# untitled.net
KiCad netlist of a schematic drawn in EAGLE
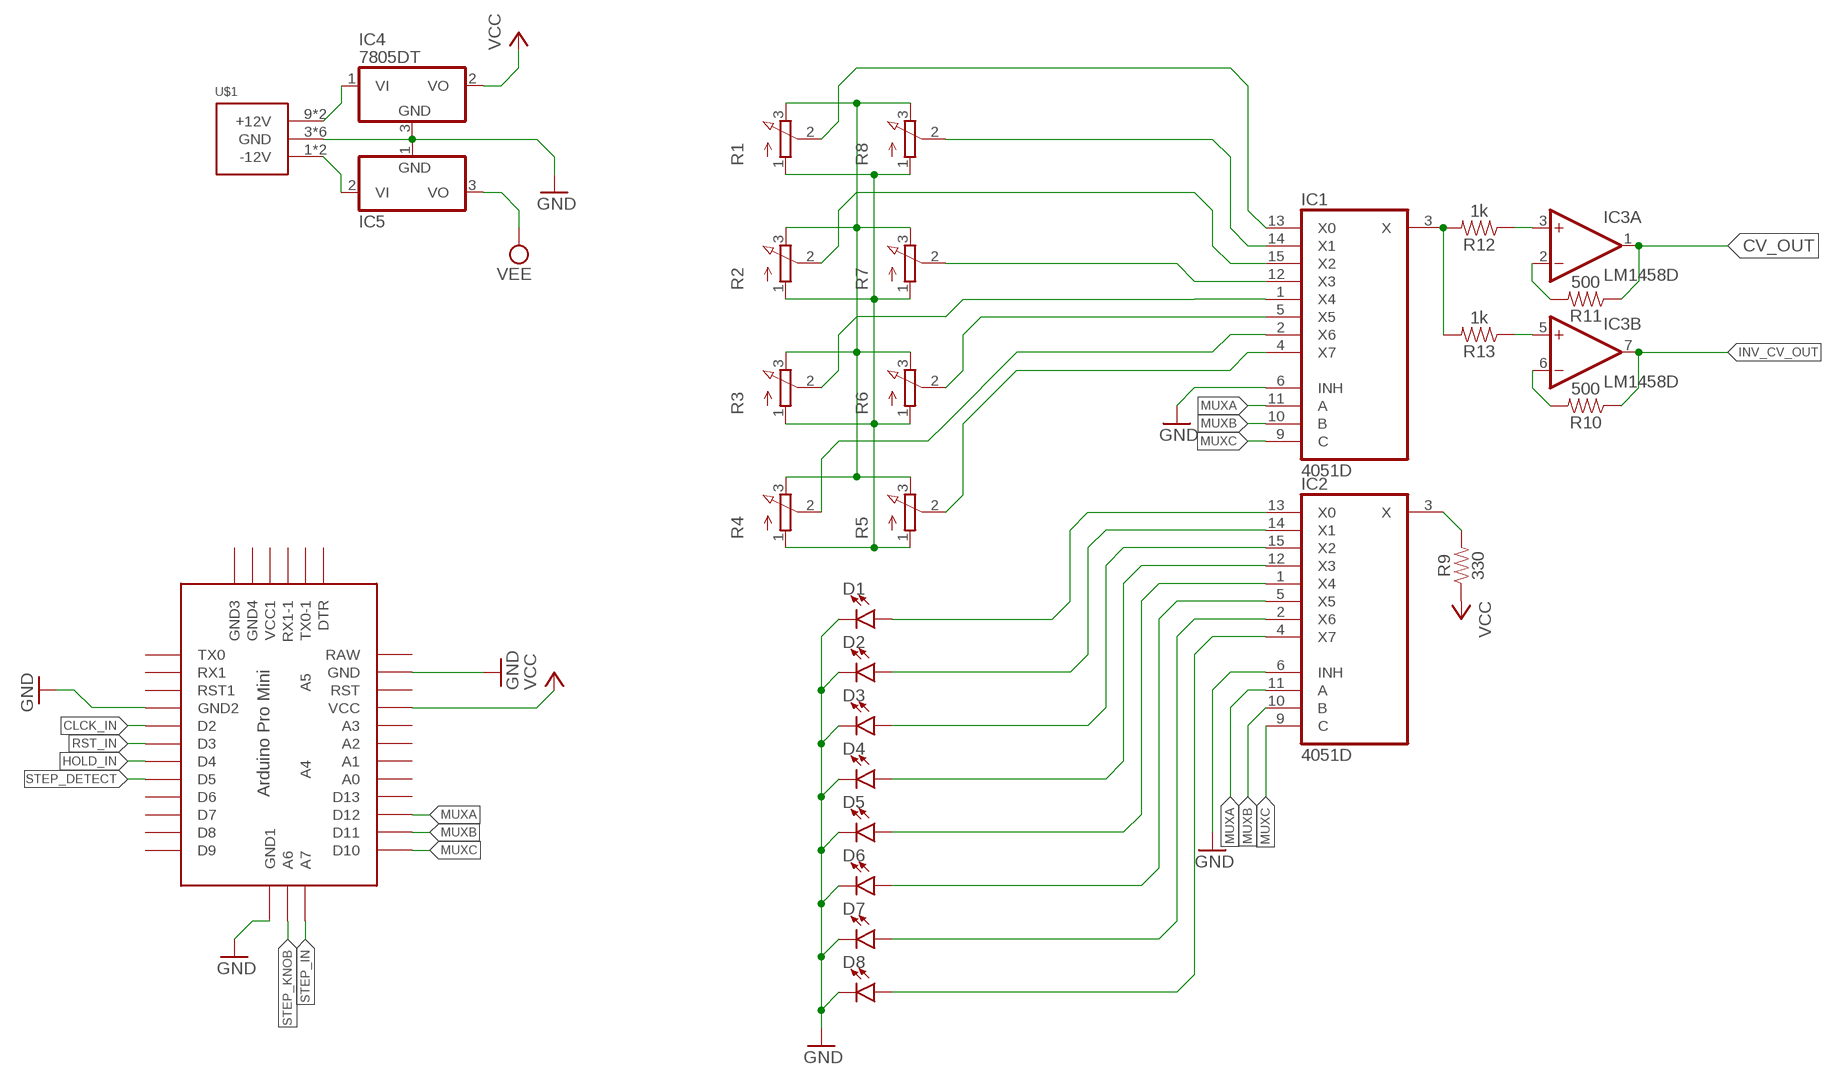
[diagram p0: schematic, sheet 1]

(export (version "E")
  (design (tool "Eeschema 10.0.6"))
  (components
    (comp (ref "D1")
      (value "LED5MM")
      (footprint "eagle-import:LED_5MM")
      (libsource (lib "eagle-import") (part "LED5MM"))
    )
    (comp (ref "D2")
      (value "LED5MM")
      (footprint "eagle-import:LED_5MM")
      (libsource (lib "eagle-import") (part "LED5MM"))
    )
    (comp (ref "D3")
      (value "LED5MM")
      (footprint "eagle-import:LED_5MM")
      (libsource (lib "eagle-import") (part "LED5MM"))
    )
    (comp (ref "D4")
      (value "LED5MM")
      (footprint "eagle-import:LED_5MM")
      (libsource (lib "eagle-import") (part "LED5MM"))
    )
    (comp (ref "D5")
      (value "LED5MM")
      (footprint "eagle-import:LED_5MM")
      (libsource (lib "eagle-import") (part "LED5MM"))
    )
    (comp (ref "D6")
      (value "LED5MM")
      (footprint "eagle-import:LED_5MM")
      (libsource (lib "eagle-import") (part "LED5MM"))
    )
    (comp (ref "D7")
      (value "LED5MM")
      (footprint "eagle-import:LED_5MM")
      (libsource (lib "eagle-import") (part "LED5MM"))
    )
    (comp (ref "D8")
      (value "LED5MM")
      (footprint "eagle-import:LED_5MM")
      (libsource (lib "eagle-import") (part "LED5MM"))
    )
    (comp (ref "IC1")
      (value "4051D")
      (footprint "eagle-import:SO16")
      (libsource (lib "eagle-import") (part "4051D"))
    )
    (comp (ref "IC2")
      (value "4051D")
      (footprint "eagle-import:SO16")
      (libsource (lib "eagle-import") (part "4051D"))
    )
    (comp (ref "IC3")
      (value "LM1458D")
      (footprint "eagle-import:SO08")
      (libsource (lib "eagle-import") (part "1458DLM"))
    )
    (comp (ref "IC4")
      (value "7805DT")
      (footprint "eagle-import:TO252")
      (libsource (lib "eagle-import") (part "78DT05"))
    )
    (comp (ref "IC5")
      (value "7905T")
      (footprint "eagle-import:TO220H")
      (libsource (lib "eagle-import") (part "79T05"))
    )
    (comp (ref "R1")
      (value "3RP/1610N")
      (footprint "eagle-import:3RP_1610N")
      (libsource (lib "eagle-import") (part "3RP/1610N"))
    )
    (comp (ref "R2")
      (value "3RP/1610N")
      (footprint "eagle-import:3RP_1610N")
      (libsource (lib "eagle-import") (part "3RP/1610N"))
    )
    (comp (ref "R3")
      (value "3RP/1610N")
      (footprint "eagle-import:3RP_1610N")
      (libsource (lib "eagle-import") (part "3RP/1610N"))
    )
    (comp (ref "R4")
      (value "3RP/1610N")
      (footprint "eagle-import:3RP_1610N")
      (libsource (lib "eagle-import") (part "3RP/1610N"))
    )
    (comp (ref "R5")
      (value "3RP/1610N")
      (footprint "eagle-import:3RP_1610N")
      (libsource (lib "eagle-import") (part "3RP/1610N"))
    )
    (comp (ref "R6")
      (value "3RP/1610N")
      (footprint "eagle-import:3RP_1610N")
      (libsource (lib "eagle-import") (part "3RP/1610N"))
    )
    (comp (ref "R7")
      (value "3RP/1610N")
      (footprint "eagle-import:3RP_1610N")
      (libsource (lib "eagle-import") (part "3RP/1610N"))
    )
    (comp (ref "R8")
      (value "3RP/1610N")
      (footprint "eagle-import:3RP_1610N")
      (libsource (lib "eagle-import") (part "3RP/1610N"))
    )
    (comp (ref "R9")
      (value "330")
      (footprint "eagle-import:AXIAL-0.3")
      (libsource (lib "eagle-import") (part "330OHM-HORIZ-1/10W-5%"))
    )
    (comp (ref "R10")
      (value "500")
      (footprint "eagle-import:AXIAL-0.3")
      (libsource (lib "eagle-import") (part "330OHM-HORIZ-1/10W-5%"))
    )
    (comp (ref "R11")
      (value "500")
      (footprint "eagle-import:AXIAL-0.3")
      (libsource (lib "eagle-import") (part "330OHM-HORIZ-1/10W-5%"))
    )
    (comp (ref "R12")
      (value "1k")
      (footprint "eagle-import:AXIAL-0.3")
      (libsource (lib "eagle-import") (part "330OHM-HORIZ-1/10W-5%"))
    )
    (comp (ref "R13")
      (value "1k")
      (footprint "eagle-import:AXIAL-0.3")
      (libsource (lib "eagle-import") (part "330OHM-HORIZ-1/10W-5%"))
    )
    (comp (ref "U$1")
      (value "POWER_SIMPLE10")
      (footprint "eagle-import:POWER_10")
      (libsource (lib "eagle-import") (part "POWER_SIMPLE10"))
    )
    (comp (ref "U$2")
      (value "ABK-PRO-MINI")
      (footprint "eagle-import:ABK-PRO-MINI")
      (libsource (lib "eagle-import") (part "ABK-PRO-MINI"))
    )
  )
  (nets
    (net (code "1") (name "CLCK_IN") (class "Default")
      (node (ref "U$2") (pin "D2") (pinfunction "D2_D2") (pintype "bidirectional"))
    )
    (net (code "2") (name "CV_OUT") (class "Default")
      (node (ref "IC3") (pin "1") (pinfunction "OUT_1") (pintype "output"))
      (node (ref "R11") (pin "P$1") (pinfunction "1_P$1") (pintype "passive"))
    )
    (net (code "3") (name "GND") (class "Default")
      (node (ref "D1") (pin "K") (pinfunction "C_K") (pintype "passive"))
      (node (ref "D2") (pin "K") (pinfunction "C_K") (pintype "passive"))
      (node (ref "D3") (pin "K") (pinfunction "C_K") (pintype "passive"))
      (node (ref "D4") (pin "K") (pinfunction "C_K") (pintype "passive"))
      (node (ref "D5") (pin "K") (pinfunction "C_K") (pintype "passive"))
      (node (ref "D6") (pin "K") (pinfunction "C_K") (pintype "passive"))
      (node (ref "D7") (pin "K") (pinfunction "C_K") (pintype "passive"))
      (node (ref "D8") (pin "K") (pinfunction "C_K") (pintype "passive"))
      (node (ref "IC1") (pin "6") (pinfunction "INH_6") (pintype "input"))
      (node (ref "IC2") (pin "6") (pinfunction "INH_6") (pintype "input"))
      (node (ref "IC4") (pin "3") (pinfunction "GND_3") (pintype "passive"))
      (node (ref "IC5") (pin "1") (pinfunction "GND_1") (pintype "passive"))
      (node (ref "U$1") (pin "3") (pinfunction "GND_3") (pintype "bidirectional"))
      (node (ref "U$1") (pin "4") (pinfunction "GND_4") (pintype "bidirectional"))
      (node (ref "U$1") (pin "5") (pinfunction "GND_5") (pintype "bidirectional"))
      (node (ref "U$1") (pin "6") (pinfunction "GND_6") (pintype "bidirectional"))
      (node (ref "U$1") (pin "7") (pinfunction "GND_7") (pintype "bidirectional"))
      (node (ref "U$1") (pin "8") (pinfunction "GND_8") (pintype "bidirectional"))
      (node (ref "U$2") (pin "GND") (pinfunction "GND_GND") (pintype "bidirectional"))
      (node (ref "U$2") (pin "GND1") (pinfunction "GND2_GND1") (pintype "bidirectional"))
      (node (ref "U$2") (pin "GND4") (pinfunction "GND1_GND4") (pintype "bidirectional"))
    )
    (net (code "4") (name "HOLD_IN") (class "Default")
      (node (ref "U$2") (pin "D4") (pinfunction "D4_D4") (pintype "bidirectional"))
    )
    (net (code "5") (name "INV_CV_OUT") (class "Default")
      (node (ref "IC3") (pin "7") (pinfunction "OUT_7") (pintype "output"))
      (node (ref "R10") (pin "P$1") (pinfunction "1_P$1") (pintype "passive"))
    )
    (net (code "6") (name "MUXA") (class "Default")
      (node (ref "IC1") (pin "11") (pinfunction "A_11") (pintype "input"))
      (node (ref "IC2") (pin "11") (pinfunction "A_11") (pintype "input"))
      (node (ref "U$2") (pin "D12") (pinfunction "D12_D12") (pintype "bidirectional"))
    )
    (net (code "7") (name "MUXB") (class "Default")
      (node (ref "IC1") (pin "10") (pinfunction "B_10") (pintype "input"))
      (node (ref "IC2") (pin "10") (pinfunction "B_10") (pintype "input"))
      (node (ref "U$2") (pin "D11") (pinfunction "D11_D11") (pintype "bidirectional"))
    )
    (net (code "8") (name "MUXC") (class "Default")
      (node (ref "IC1") (pin "9") (pinfunction "C_9") (pintype "input"))
      (node (ref "IC2") (pin "9") (pinfunction "C_9") (pintype "input"))
      (node (ref "U$2") (pin "D10") (pinfunction "D10_D10") (pintype "bidirectional"))
    )
    (net (code "9") (name "Net-(IC1A-X)") (class "Default")
      (node (ref "IC1") (pin "3") (pinfunction "X_3") (pintype "bidirectional"))
      (node (ref "R12") (pin "P$2") (pinfunction "2_P$2") (pintype "passive"))
      (node (ref "R13") (pin "P$2") (pinfunction "2_P$2") (pintype "passive"))
    )
    (net (code "10") (name "Net-(IC1A-X0)") (class "Default")
      (node (ref "IC1") (pin "13") (pinfunction "X0_13") (pintype "bidirectional"))
      (node (ref "R1") (pin "2") (pinfunction "S_2") (pintype "passive"))
    )
    (net (code "11") (name "Net-(IC1A-X1)") (class "Default")
      (node (ref "IC1") (pin "14") (pinfunction "X1_14") (pintype "bidirectional"))
      (node (ref "R8") (pin "2") (pinfunction "S_2") (pintype "passive"))
    )
    (net (code "12") (name "Net-(IC1A-X2)") (class "Default")
      (node (ref "IC1") (pin "15") (pinfunction "X2_15") (pintype "bidirectional"))
      (node (ref "R2") (pin "2") (pinfunction "S_2") (pintype "passive"))
    )
    (net (code "13") (name "Net-(IC1A-X3)") (class "Default")
      (node (ref "IC1") (pin "12") (pinfunction "X3_12") (pintype "bidirectional"))
      (node (ref "R7") (pin "2") (pinfunction "S_2") (pintype "passive"))
    )
    (net (code "14") (name "Net-(IC1A-X4)") (class "Default")
      (node (ref "IC1") (pin "1") (pinfunction "X4_1") (pintype "bidirectional"))
      (node (ref "R3") (pin "2") (pinfunction "S_2") (pintype "passive"))
    )
    (net (code "15") (name "Net-(IC1A-X5)") (class "Default")
      (node (ref "IC1") (pin "5") (pinfunction "X5_5") (pintype "bidirectional"))
      (node (ref "R6") (pin "2") (pinfunction "S_2") (pintype "passive"))
    )
    (net (code "16") (name "Net-(IC1A-X6)") (class "Default")
      (node (ref "IC1") (pin "2") (pinfunction "X6_2") (pintype "bidirectional"))
      (node (ref "R4") (pin "2") (pinfunction "S_2") (pintype "passive"))
    )
    (net (code "17") (name "Net-(IC1A-X7)") (class "Default")
      (node (ref "IC1") (pin "4") (pinfunction "X7_4") (pintype "bidirectional"))
      (node (ref "R5") (pin "2") (pinfunction "S_2") (pintype "passive"))
    )
    (net (code "18") (name "Net-(IC2A-X)") (class "Default")
      (node (ref "IC2") (pin "3") (pinfunction "X_3") (pintype "bidirectional"))
      (node (ref "R9") (pin "P$2") (pinfunction "2_P$2") (pintype "passive"))
    )
    (net (code "19") (name "Net-(IC2A-X0)") (class "Default")
      (node (ref "D1") (pin "A") (pinfunction "A_A") (pintype "passive"))
      (node (ref "IC2") (pin "13") (pinfunction "X0_13") (pintype "bidirectional"))
    )
    (net (code "20") (name "Net-(IC2A-X1)") (class "Default")
      (node (ref "D2") (pin "A") (pinfunction "A_A") (pintype "passive"))
      (node (ref "IC2") (pin "14") (pinfunction "X1_14") (pintype "bidirectional"))
    )
    (net (code "21") (name "Net-(IC2A-X2)") (class "Default")
      (node (ref "D3") (pin "A") (pinfunction "A_A") (pintype "passive"))
      (node (ref "IC2") (pin "15") (pinfunction "X2_15") (pintype "bidirectional"))
    )
    (net (code "22") (name "Net-(IC2A-X3)") (class "Default")
      (node (ref "D4") (pin "A") (pinfunction "A_A") (pintype "passive"))
      (node (ref "IC2") (pin "12") (pinfunction "X3_12") (pintype "bidirectional"))
    )
    (net (code "23") (name "Net-(IC2A-X4)") (class "Default")
      (node (ref "D5") (pin "A") (pinfunction "A_A") (pintype "passive"))
      (node (ref "IC2") (pin "1") (pinfunction "X4_1") (pintype "bidirectional"))
    )
    (net (code "24") (name "Net-(IC2A-X5)") (class "Default")
      (node (ref "D6") (pin "A") (pinfunction "A_A") (pintype "passive"))
      (node (ref "IC2") (pin "5") (pinfunction "X5_5") (pintype "bidirectional"))
    )
    (net (code "25") (name "Net-(IC2A-X6)") (class "Default")
      (node (ref "D7") (pin "A") (pinfunction "A_A") (pintype "passive"))
      (node (ref "IC2") (pin "2") (pinfunction "X6_2") (pintype "bidirectional"))
    )
    (net (code "26") (name "Net-(IC2A-X7)") (class "Default")
      (node (ref "D8") (pin "A") (pinfunction "A_A") (pintype "passive"))
      (node (ref "IC2") (pin "4") (pinfunction "X7_4") (pintype "bidirectional"))
    )
    (net (code "27") (name "Net-(IC3A-+IN)") (class "Default")
      (node (ref "IC3") (pin "3") (pinfunction "+IN_3") (pintype "input"))
      (node (ref "R12") (pin "P$1") (pinfunction "1_P$1") (pintype "passive"))
    )
    (net (code "28") (name "Net-(IC3A--IN)") (class "Default")
      (node (ref "IC3") (pin "2") (pinfunction "-IN_2") (pintype "input"))
      (node (ref "R11") (pin "P$2") (pinfunction "2_P$2") (pintype "passive"))
    )
    (net (code "29") (name "Net-(IC3B-+IN)") (class "Default")
      (node (ref "IC3") (pin "5") (pinfunction "+IN_5") (pintype "input"))
      (node (ref "R13") (pin "P$1") (pinfunction "1_P$1") (pintype "passive"))
    )
    (net (code "30") (name "Net-(IC3B--IN)") (class "Default")
      (node (ref "IC3") (pin "6") (pinfunction "-IN_6") (pintype "input"))
      (node (ref "R10") (pin "P$2") (pinfunction "2_P$2") (pintype "passive"))
    )
    (net (code "31") (name "Net-(IC4-VI)") (class "Default")
      (node (ref "IC4") (pin "1") (pinfunction "VI_1") (pintype "input"))
      (node (ref "U$1") (pin "10") (pinfunction "+12V_10") (pintype "bidirectional"))
      (node (ref "U$1") (pin "9") (pinfunction "+12V_9") (pintype "bidirectional"))
    )
    (net (code "32") (name "Net-(IC5-VI)") (class "Default")
      (node (ref "IC5") (pin "2") (pinfunction "VI_2") (pintype "input"))
      (node (ref "U$1") (pin "1") (pinfunction "-12V_1") (pintype "bidirectional"))
      (node (ref "U$1") (pin "2") (pinfunction "-12V_2") (pintype "bidirectional"))
    )
    (net (code "33") (name "Net-(R1-A)") (class "Default")
      (node (ref "R1") (pin "1") (pinfunction "A_1") (pintype "passive"))
      (node (ref "R2") (pin "1") (pinfunction "A_1") (pintype "passive"))
      (node (ref "R3") (pin "1") (pinfunction "A_1") (pintype "passive"))
      (node (ref "R4") (pin "1") (pinfunction "A_1") (pintype "passive"))
      (node (ref "R5") (pin "1") (pinfunction "A_1") (pintype "passive"))
      (node (ref "R6") (pin "1") (pinfunction "A_1") (pintype "passive"))
      (node (ref "R7") (pin "1") (pinfunction "A_1") (pintype "passive"))
      (node (ref "R8") (pin "1") (pinfunction "A_1") (pintype "passive"))
    )
    (net (code "34") (name "Net-(R1-E)") (class "Default")
      (node (ref "R1") (pin "3") (pinfunction "E_3") (pintype "passive"))
      (node (ref "R2") (pin "3") (pinfunction "E_3") (pintype "passive"))
      (node (ref "R3") (pin "3") (pinfunction "E_3") (pintype "passive"))
      (node (ref "R4") (pin "3") (pinfunction "E_3") (pintype "passive"))
      (node (ref "R5") (pin "3") (pinfunction "E_3") (pintype "passive"))
      (node (ref "R6") (pin "3") (pinfunction "E_3") (pintype "passive"))
      (node (ref "R7") (pin "3") (pinfunction "E_3") (pintype "passive"))
      (node (ref "R8") (pin "3") (pinfunction "E_3") (pintype "passive"))
    )
    (net (code "35") (name "RST_IN") (class "Default")
      (node (ref "U$2") (pin "D3") (pinfunction "D3_D3") (pintype "bidirectional"))
    )
    (net (code "36") (name "STEP_DETECT") (class "Default")
      (node (ref "U$2") (pin "D5") (pinfunction "D5_D5") (pintype "bidirectional"))
    )
    (net (code "37") (name "STEP_IN") (class "Default")
      (node (ref "U$2") (pin "A7") (pinfunction "A7_A7") (pintype "bidirectional"))
    )
    (net (code "38") (name "STEP_KNOB") (class "Default")
      (node (ref "U$2") (pin "A6") (pinfunction "A6_A6") (pintype "bidirectional"))
    )
    (net (code "39") (name "VCC") (class "Default")
      (node (ref "IC4") (pin "2") (pinfunction "VO_2") (pintype "passive"))
      (node (ref "R9") (pin "P$1") (pinfunction "1_P$1") (pintype "passive"))
      (node (ref "U$2") (pin "VCC") (pinfunction "VCC_VCC") (pintype "bidirectional"))
    )
    (net (code "40") (name "VEE") (class "Default")
      (node (ref "IC5") (pin "3") (pinfunction "VO_3") (pintype "passive"))
    )
    (net (code "41") (name "unconnected-(U$2-GND3-PadGND2)") (class "Default")
      (node (ref "U$2") (pin "GND2") (pinfunction "GND3_GND2") (pintype "bidirectional"))
    )
    (net (code "42") (name "unconnected-(U$2-GND4-PadGND3)") (class "Default")
      (node (ref "U$2") (pin "GND3") (pinfunction "GND4_GND3") (pintype "bidirectional"))
    )
    (net (code "43") (name "unconnected-(U$2-PadA0)") (class "Default")
      (node (ref "U$2") (pin "A0") (pinfunction "A0_A0") (pintype "bidirectional"))
    )
    (net (code "44") (name "unconnected-(U$2-PadA1)") (class "Default")
      (node (ref "U$2") (pin "A1") (pinfunction "A1_A1") (pintype "bidirectional"))
    )
    (net (code "45") (name "unconnected-(U$2-PadA2)") (class "Default")
      (node (ref "U$2") (pin "A2") (pinfunction "A2_A2") (pintype "bidirectional"))
    )
    (net (code "46") (name "unconnected-(U$2-PadA3)") (class "Default")
      (node (ref "U$2") (pin "A3") (pinfunction "A3_A3") (pintype "bidirectional"))
    )
    (net (code "47") (name "unconnected-(U$2-PadA4)") (class "Default")
      (node (ref "U$2") (pin "A4") (pinfunction "A4_A4") (pintype "bidirectional"))
    )
    (net (code "48") (name "unconnected-(U$2-PadA5)") (class "Default")
      (node (ref "U$2") (pin "A5") (pinfunction "A5_A5") (pintype "bidirectional"))
    )
    (net (code "49") (name "unconnected-(U$2-PadD6)") (class "Default")
      (node (ref "U$2") (pin "D6") (pinfunction "D6_D6") (pintype "bidirectional"))
    )
    (net (code "50") (name "unconnected-(U$2-PadD7)") (class "Default")
      (node (ref "U$2") (pin "D7") (pinfunction "D7_D7") (pintype "bidirectional"))
    )
    (net (code "51") (name "unconnected-(U$2-PadD8)") (class "Default")
      (node (ref "U$2") (pin "D8") (pinfunction "D8_D8") (pintype "bidirectional"))
    )
    (net (code "52") (name "unconnected-(U$2-PadD9)") (class "Default")
      (node (ref "U$2") (pin "D9") (pinfunction "D9_D9") (pintype "bidirectional"))
    )
    (net (code "53") (name "unconnected-(U$2-PadD13)") (class "Default")
      (node (ref "U$2") (pin "D13") (pinfunction "D13_D13") (pintype "bidirectional"))
    )
    (net (code "54") (name "unconnected-(U$2-PadDTR)") (class "Default")
      (node (ref "U$2") (pin "DTR") (pinfunction "DTR_DTR") (pintype "bidirectional"))
    )
    (net (code "55") (name "unconnected-(U$2-PadRAW)") (class "Default")
      (node (ref "U$2") (pin "RAW") (pinfunction "RAW_RAW") (pintype "bidirectional"))
    )
    (net (code "56") (name "unconnected-(U$2-PadRST)") (class "Default")
      (node (ref "U$2") (pin "RST") (pinfunction "RST_RST") (pintype "bidirectional"))
    )
    (net (code "57") (name "unconnected-(U$2-PadRST1)") (class "Default")
      (node (ref "U$2") (pin "RST1") (pinfunction "RST1_RST1") (pintype "bidirectional"))
    )
    (net (code "58") (name "unconnected-(U$2-PadRX1)") (class "Default")
      (node (ref "U$2") (pin "RX1") (pinfunction "RX1_RX1") (pintype "bidirectional"))
    )
    (net (code "59") (name "unconnected-(U$2-PadRX1-1)") (class "Default")
      (node (ref "U$2") (pin "RX1-1") (pinfunction "RX1-1_RX1-1") (pintype "bidirectional"))
    )
    (net (code "60") (name "unconnected-(U$2-PadTX0)") (class "Default")
      (node (ref "U$2") (pin "TX0") (pinfunction "TX0_TX0") (pintype "bidirectional"))
    )
    (net (code "61") (name "unconnected-(U$2-PadTX0-1)") (class "Default")
      (node (ref "U$2") (pin "TX0-1") (pinfunction "TX0-1_TX0-1") (pintype "bidirectional"))
    )
    (net (code "62") (name "unconnected-(U$2-PadVCC1)") (class "Default")
      (node (ref "U$2") (pin "VCC1") (pinfunction "VCC1_VCC1") (pintype "bidirectional"))
    )
  )
)
